# schematics.net
KiCad netlist of a schematic drawn in EAGLE
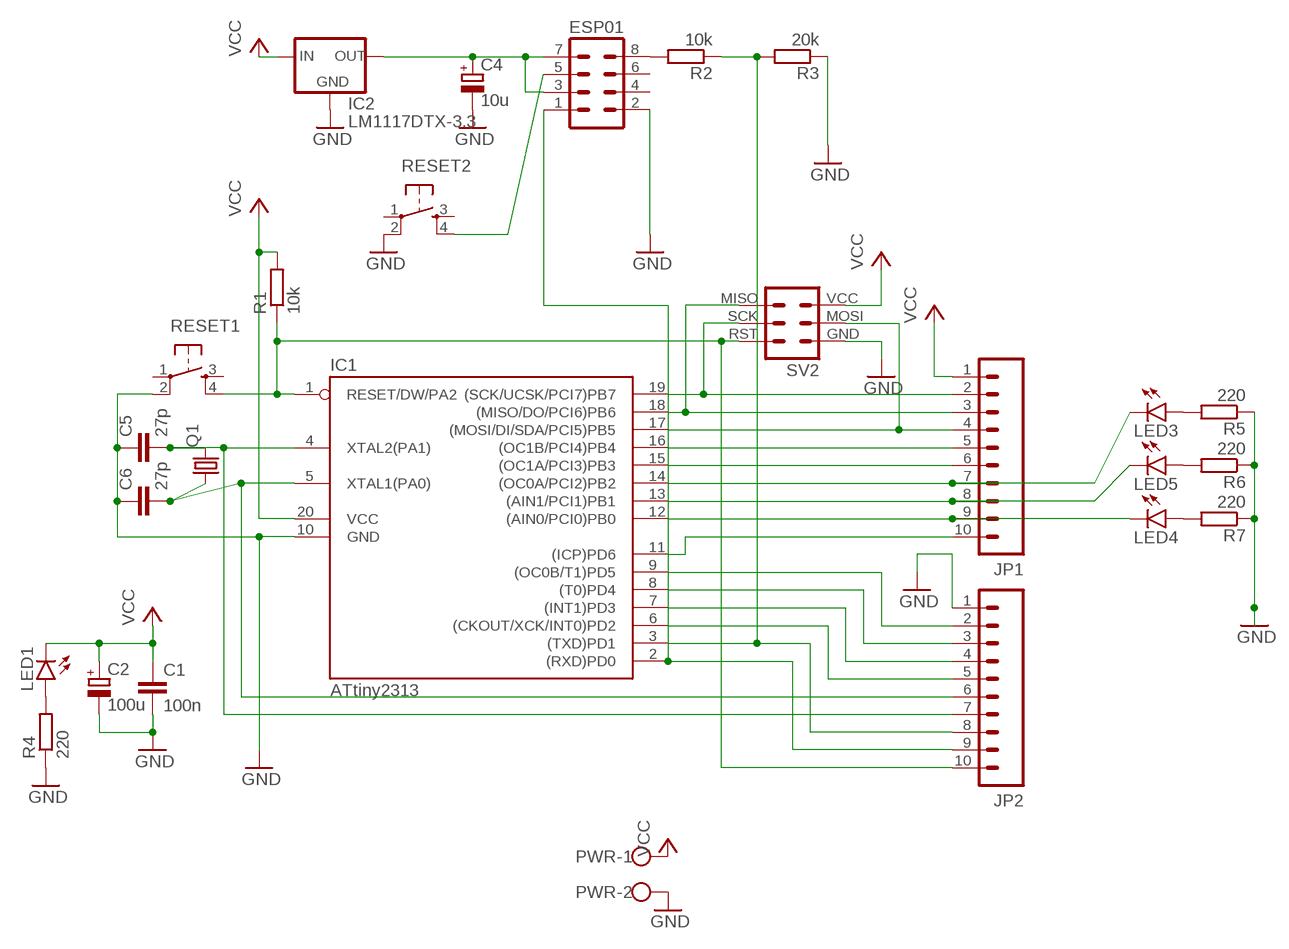
[diagram p0: schematic, sheet 1]

(export (version "E")
  (design (tool "Eeschema 10.0.6"))
  (components
    (comp (ref "C1")
      (value "100n")
      (footprint "eagle-import:C025-025X050")
      (libsource (lib "eagle-import") (part "C-EU025-025X050"))
    )
    (comp (ref "C2")
      (value "100u")
      (footprint "eagle-import:E2,5-5")
      (libsource (lib "eagle-import") (part "CPOL-EUE2.5-5"))
    )
    (comp (ref "C4")
      (value "10u")
      (footprint "eagle-import:E2,5-5")
      (libsource (lib "eagle-import") (part "CPOL-EUE2.5-5"))
    )
    (comp (ref "C5")
      (value "27p")
      (footprint "eagle-import:C2.5-2")
      (libsource (lib "eagle-import") (part "C2.5/2"))
    )
    (comp (ref "C6")
      (value "27p")
      (footprint "eagle-import:C2.5-2")
      (libsource (lib "eagle-import") (part "C2.5/2"))
    )
    (comp (ref "ESP01")
      (value "MA04-2")
      (footprint "eagle-import:MA04-2")
      (libsource (lib "eagle-import") (part "MA04-2"))
    )
    (comp (ref "IC1")
      (value "ATtiny2313")
      (footprint "eagle-import:DIL20")
      (libsource (lib "eagle-import") (part "ATTINY2313P-20"))
    )
    (comp (ref "IC2")
      (value "LM1117DTX-3.3")
      (footprint "eagle-import:TO252")
      (libsource (lib "eagle-import") (part "LM1117DTX-3.3"))
    )
    (comp (ref "JP1")
      (value "M100.1")
      (footprint "eagle-import:1X10")
      (libsource (lib "eagle-import") (part "M100.1"))
    )
    (comp (ref "JP2")
      (value "M100.1")
      (footprint "eagle-import:1X10")
      (libsource (lib "eagle-import") (part "M100.1"))
    )
    (comp (ref "LED1")
      (value "LED3MM")
      (footprint "eagle-import:LED3MM")
      (libsource (lib "eagle-import") (part "LED3MM"))
    )
    (comp (ref "LED3")
      (value "LED3MM")
      (footprint "eagle-import:LED3MM")
      (libsource (lib "eagle-import") (part "LED3MM"))
    )
    (comp (ref "LED4")
      (value "LED3MM")
      (footprint "eagle-import:LED3MM")
      (libsource (lib "eagle-import") (part "LED3MM"))
    )
    (comp (ref "LED5")
      (value "LED3MM")
      (footprint "eagle-import:LED3MM")
      (libsource (lib "eagle-import") (part "LED3MM"))
    )
    (comp (ref "PWR")
      (value "W237-102")
      (footprint "eagle-import:W237-102")
      (fields (field (name "MPN") "237-102"))
      (libsource (lib "eagle-import") (part "W237-102"))
    )
    (comp (ref "Q1")
      (value "CRYSTALHC49S")
      (footprint "eagle-import:HC49_S")
      (libsource (lib "eagle-import") (part "CRYSTALHC49S"))
    )
    (comp (ref "R1")
      (value "10k")
      (footprint "eagle-import:0207_5V")
      (libsource (lib "eagle-import") (part "R-EU_0207/5V"))
    )
    (comp (ref "R2")
      (value "10k")
      (footprint "eagle-import:0207_5V")
      (libsource (lib "eagle-import") (part "R-EU_0207/5V"))
    )
    (comp (ref "R3")
      (value "20k")
      (footprint "eagle-import:0207_5V")
      (libsource (lib "eagle-import") (part "R-EU_0207/5V"))
    )
    (comp (ref "R4")
      (value "220")
      (footprint "eagle-import:0207_5V")
      (libsource (lib "eagle-import") (part "R-EU_0207/5V"))
    )
    (comp (ref "R5")
      (value "220")
      (footprint "eagle-import:0207_5V")
      (libsource (lib "eagle-import") (part "R-EU_0207/5V"))
    )
    (comp (ref "R6")
      (value "220")
      (footprint "eagle-import:0207_5V")
      (libsource (lib "eagle-import") (part "R-EU_0207/5V"))
    )
    (comp (ref "R7")
      (value "220")
      (footprint "eagle-import:0207_5V")
      (libsource (lib "eagle-import") (part "R-EU_0207/5V"))
    )
    (comp (ref "RESET1")
      (value "TAC_SWITCHPTH")
      (footprint "eagle-import:TACTILE-PTH")
      (libsource (lib "eagle-import") (part "TAC_SWITCHPTH"))
    )
    (comp (ref "RESET2")
      (value "TAC_SWITCHPTH")
      (footprint "eagle-import:TACTILE-PTH")
      (libsource (lib "eagle-import") (part "TAC_SWITCHPTH"))
    )
    (comp (ref "SV2")
      (value "MA03-2")
      (footprint "eagle-import:MA03-2")
      (libsource (lib "eagle-import") (part "MA03-2"))
    )
  )
  (nets
    (net (code "1") (name "GND") (class "Default")
      (node (ref "C1") (pin "2") (pinfunction "2_2") (pintype "passive"))
      (node (ref "C2") (pin "-") (pinfunction "-_-") (pintype "passive"))
      (node (ref "C4") (pin "-") (pinfunction "-_-") (pintype "passive"))
      (node (ref "C5") (pin "1") (pinfunction "1_1") (pintype "passive"))
      (node (ref "C6") (pin "1") (pinfunction "1_1") (pintype "passive"))
      (node (ref "ESP01") (pin "2") (pinfunction "2_2") (pintype "passive"))
      (node (ref "IC1") (pin "10") (pinfunction "GND_10") (pintype "power_in"))
      (node (ref "IC2") (pin "1") (pinfunction "GND_1") (pintype "input"))
      (node (ref "JP2") (pin "1") (pinfunction "1_1") (pintype "passive"))
      (node (ref "PWR") (pin "2") (pinfunction "KL_2") (pintype "passive"))
      (node (ref "R3") (pin "1") (pinfunction "1_1") (pintype "passive"))
      (node (ref "R4") (pin "1") (pinfunction "1_1") (pintype "passive"))
      (node (ref "R5") (pin "1") (pinfunction "1_1") (pintype "passive"))
      (node (ref "R6") (pin "1") (pinfunction "1_1") (pintype "passive"))
      (node (ref "R7") (pin "1") (pinfunction "1_1") (pintype "passive"))
      (node (ref "RESET1") (pin "2") (pinfunction "2_2") (pintype "passive"))
      (node (ref "RESET2") (pin "2") (pinfunction "2_2") (pintype "passive"))
      (node (ref "SV2") (pin "GND") (pinfunction "GND_GND") (pintype "passive"))
    )
    (net (code "2") (name "Net-(ESP01-Pad5)") (class "Default")
      (node (ref "ESP01") (pin "5") (pinfunction "5_5") (pintype "passive"))
      (node (ref "RESET2") (pin "4") (pinfunction "4_4") (pintype "passive"))
    )
    (net (code "3") (name "Net-(ESP01-Pad8)") (class "Default")
      (node (ref "ESP01") (pin "8") (pinfunction "8_8") (pintype "passive"))
      (node (ref "R2") (pin "2") (pinfunction "2_2") (pintype "passive"))
    )
    (net (code "4") (name "Net-(IC1-(AIN0{slash}PCI0)PB0)") (class "Default")
      (node (ref "IC1") (pin "12") (pinfunction "(AIN0/PCI0)PB0_12") (pintype "bidirectional"))
      (node (ref "JP1") (pin "9") (pinfunction "9_9") (pintype "passive"))
      (node (ref "LED4") (pin "K") (pinfunction "C_K") (pintype "passive"))
    )
    (net (code "5") (name "Net-(IC1-(AIN1{slash}PCI1)PB1)") (class "Default")
      (node (ref "IC1") (pin "13") (pinfunction "(AIN1/PCI1)PB1_13") (pintype "bidirectional"))
      (node (ref "JP1") (pin "8") (pinfunction "8_8") (pintype "passive"))
      (node (ref "LED5") (pin "K") (pinfunction "C_K") (pintype "passive"))
    )
    (net (code "6") (name "Net-(IC1-(CKOUT{slash}XCK{slash}INT0)PD2)") (class "Default")
      (node (ref "IC1") (pin "6") (pinfunction "(CKOUT/XCK/INT0)PD2_6") (pintype "bidirectional"))
      (node (ref "JP2") (pin "5") (pinfunction "5_5") (pintype "passive"))
    )
    (net (code "7") (name "Net-(IC1-(ICP)PD6)") (class "Default")
      (node (ref "IC1") (pin "11") (pinfunction "(ICP)PD6_11") (pintype "bidirectional"))
      (node (ref "JP1") (pin "10") (pinfunction "10_10") (pintype "passive"))
    )
    (net (code "8") (name "Net-(IC1-(INT1)PD3)") (class "Default")
      (node (ref "IC1") (pin "7") (pinfunction "(INT1)PD3_7") (pintype "bidirectional"))
      (node (ref "JP2") (pin "4") (pinfunction "4_4") (pintype "passive"))
    )
    (net (code "9") (name "Net-(IC1-(MISO{slash}DO{slash}PCI6)PB6)") (class "Default")
      (node (ref "IC1") (pin "18") (pinfunction "(MISO/DO/PCI6)PB6_18") (pintype "bidirectional"))
      (node (ref "JP1") (pin "3") (pinfunction "3_3") (pintype "passive"))
      (node (ref "SV2") (pin "MISO") (pinfunction "MISO_MISO") (pintype "passive"))
    )
    (net (code "10") (name "Net-(IC1-(MOSI{slash}DI{slash}SDA{slash}PCI5)PB5)") (class "Default")
      (node (ref "IC1") (pin "17") (pinfunction "(MOSI/DI/SDA/PCI5)PB5_17") (pintype "bidirectional"))
      (node (ref "JP1") (pin "4") (pinfunction "4_4") (pintype "passive"))
      (node (ref "SV2") (pin "MOSI") (pinfunction "MOSI_MOSI") (pintype "passive"))
    )
    (net (code "11") (name "Net-(IC1-(OC0A{slash}PCI2)PB2)") (class "Default")
      (node (ref "IC1") (pin "14") (pinfunction "(OC0A/PCI2)PB2_14") (pintype "bidirectional"))
      (node (ref "JP1") (pin "7") (pinfunction "7_7") (pintype "passive"))
      (node (ref "LED3") (pin "K") (pinfunction "C_K") (pintype "passive"))
    )
    (net (code "12") (name "Net-(IC1-(OC0B{slash}T1)PD5)") (class "Default")
      (node (ref "IC1") (pin "9") (pinfunction "(OC0B/T1)PD5_9") (pintype "bidirectional"))
      (node (ref "JP2") (pin "2") (pinfunction "2_2") (pintype "passive"))
    )
    (net (code "13") (name "Net-(IC1-(OC1A{slash}PCI3)PB3)") (class "Default")
      (node (ref "IC1") (pin "15") (pinfunction "(OC1A/PCI3)PB3_15") (pintype "bidirectional"))
      (node (ref "JP1") (pin "6") (pinfunction "6_6") (pintype "passive"))
    )
    (net (code "14") (name "Net-(IC1-(OC1B{slash}PCI4)PB4)") (class "Default")
      (node (ref "IC1") (pin "16") (pinfunction "(OC1B/PCI4)PB4_16") (pintype "bidirectional"))
      (node (ref "JP1") (pin "5") (pinfunction "5_5") (pintype "passive"))
    )
    (net (code "15") (name "Net-(IC1-(RXD)PD0)") (class "Default")
      (node (ref "ESP01") (pin "1") (pinfunction "1_1") (pintype "passive"))
      (node (ref "IC1") (pin "2") (pinfunction "(RXD)PD0_2") (pintype "bidirectional"))
      (node (ref "JP2") (pin "9") (pinfunction "9_9") (pintype "passive"))
    )
    (net (code "16") (name "Net-(IC1-(SCK{slash}UCSK{slash}PCI7)PB7)") (class "Default")
      (node (ref "IC1") (pin "19") (pinfunction "(SCK/UCSK/PCI7)PB7_19") (pintype "bidirectional"))
      (node (ref "JP1") (pin "2") (pinfunction "2_2") (pintype "passive"))
      (node (ref "SV2") (pin "SCK") (pinfunction "SCK_SCK") (pintype "passive"))
    )
    (net (code "17") (name "Net-(IC1-(T0)PD4)") (class "Default")
      (node (ref "IC1") (pin "8") (pinfunction "(T0)PD4_8") (pintype "bidirectional"))
      (node (ref "JP2") (pin "3") (pinfunction "3_3") (pintype "passive"))
    )
    (net (code "18") (name "Net-(IC1-(TXD)PD1)") (class "Default")
      (node (ref "IC1") (pin "3") (pinfunction "(TXD)PD1_3") (pintype "bidirectional"))
      (node (ref "JP2") (pin "8") (pinfunction "8_8") (pintype "passive"))
      (node (ref "R2") (pin "1") (pinfunction "1_1") (pintype "passive"))
      (node (ref "R3") (pin "2") (pinfunction "2_2") (pintype "passive"))
    )
    (net (code "19") (name "Net-(IC1-RESET{slash}DW{slash}PA2)") (class "Default")
      (node (ref "IC1") (pin "1") (pinfunction "RESET/DW/PA2_1") (pintype "bidirectional"))
      (node (ref "JP2") (pin "10") (pinfunction "10_10") (pintype "passive"))
      (node (ref "R1") (pin "1") (pinfunction "1_1") (pintype "passive"))
      (node (ref "RESET1") (pin "4") (pinfunction "4_4") (pintype "passive"))
      (node (ref "SV2") (pin "RST") (pinfunction "RST_RST") (pintype "passive"))
    )
    (net (code "20") (name "Net-(IC1-XTAL1(PA0))") (class "Default")
      (node (ref "C6") (pin "2") (pinfunction "2_2") (pintype "passive"))
      (node (ref "IC1") (pin "5") (pinfunction "XTAL1(PA0)_5") (pintype "bidirectional"))
      (node (ref "JP2") (pin "6") (pinfunction "6_6") (pintype "passive"))
      (node (ref "Q1") (pin "1") (pinfunction "1_1") (pintype "passive"))
    )
    (net (code "21") (name "Net-(IC1-XTAL2(PA1))") (class "Default")
      (node (ref "C5") (pin "2") (pinfunction "2_2") (pintype "passive"))
      (node (ref "IC1") (pin "4") (pinfunction "XTAL2(PA1)_4") (pintype "bidirectional"))
      (node (ref "JP2") (pin "7") (pinfunction "7_7") (pintype "passive"))
      (node (ref "Q1") (pin "2") (pinfunction "2_2") (pintype "passive"))
    )
    (net (code "22") (name "Net-(IC2-OUT)") (class "Default")
      (node (ref "C4") (pin "+") (pinfunction "+_+") (pintype "passive"))
      (node (ref "ESP01") (pin "3") (pinfunction "3_3") (pintype "passive"))
      (node (ref "ESP01") (pin "7") (pinfunction "7_7") (pintype "passive"))
      (node (ref "IC2") (pin "TAB") (pinfunction "OUT_TAB") (pintype "passive"))
    )
    (net (code "23") (name "Net-(LED1-PadA)") (class "Default")
      (node (ref "LED1") (pin "A") (pinfunction "A_A") (pintype "passive"))
      (node (ref "R4") (pin "2") (pinfunction "2_2") (pintype "passive"))
    )
    (net (code "24") (name "Net-(LED3-PadA)") (class "Default")
      (node (ref "LED3") (pin "A") (pinfunction "A_A") (pintype "passive"))
      (node (ref "R5") (pin "2") (pinfunction "2_2") (pintype "passive"))
    )
    (net (code "25") (name "Net-(LED4-PadA)") (class "Default")
      (node (ref "LED4") (pin "A") (pinfunction "A_A") (pintype "passive"))
      (node (ref "R7") (pin "2") (pinfunction "2_2") (pintype "passive"))
    )
    (net (code "26") (name "Net-(LED5-PadA)") (class "Default")
      (node (ref "LED5") (pin "A") (pinfunction "A_A") (pintype "passive"))
      (node (ref "R6") (pin "2") (pinfunction "2_2") (pintype "passive"))
    )
    (net (code "27") (name "VCC") (class "Default")
      (node (ref "C1") (pin "1") (pinfunction "1_1") (pintype "passive"))
      (node (ref "C2") (pin "+") (pinfunction "+_+") (pintype "passive"))
      (node (ref "IC1") (pin "20") (pinfunction "VCC_20") (pintype "power_in"))
      (node (ref "IC2") (pin "2") (pinfunction "IN_2") (pintype "input"))
      (node (ref "JP1") (pin "1") (pinfunction "1_1") (pintype "passive"))
      (node (ref "LED1") (pin "K") (pinfunction "C_K") (pintype "passive"))
      (node (ref "PWR") (pin "1") (pinfunction "KL_1") (pintype "passive"))
      (node (ref "R1") (pin "2") (pinfunction "2_2") (pintype "passive"))
      (node (ref "SV2") (pin "VCC") (pinfunction "VCC_VCC") (pintype "passive"))
    )
    (net (code "28") (name "unconnected-(ESP01-Pad4)") (class "Default")
      (node (ref "ESP01") (pin "4") (pinfunction "4_4") (pintype "passive"))
    )
    (net (code "29") (name "unconnected-(ESP01-Pad6)") (class "Default")
      (node (ref "ESP01") (pin "6") (pinfunction "6_6") (pintype "passive"))
    )
    (net (code "30") (name "unconnected-(RESET1-Pad1)") (class "Default")
      (node (ref "RESET1") (pin "1") (pinfunction "1_1") (pintype "passive"))
    )
    (net (code "31") (name "unconnected-(RESET1-Pad3)") (class "Default")
      (node (ref "RESET1") (pin "3") (pinfunction "3_3") (pintype "passive"))
    )
    (net (code "32") (name "unconnected-(RESET2-Pad1)") (class "Default")
      (node (ref "RESET2") (pin "1") (pinfunction "1_1") (pintype "passive"))
    )
    (net (code "33") (name "unconnected-(RESET2-Pad3)") (class "Default")
      (node (ref "RESET2") (pin "3") (pinfunction "3_3") (pintype "passive"))
    )
  )
)
